# 100tqfpBreakout.net
KiCad netlist of a schematic drawn in EAGLE
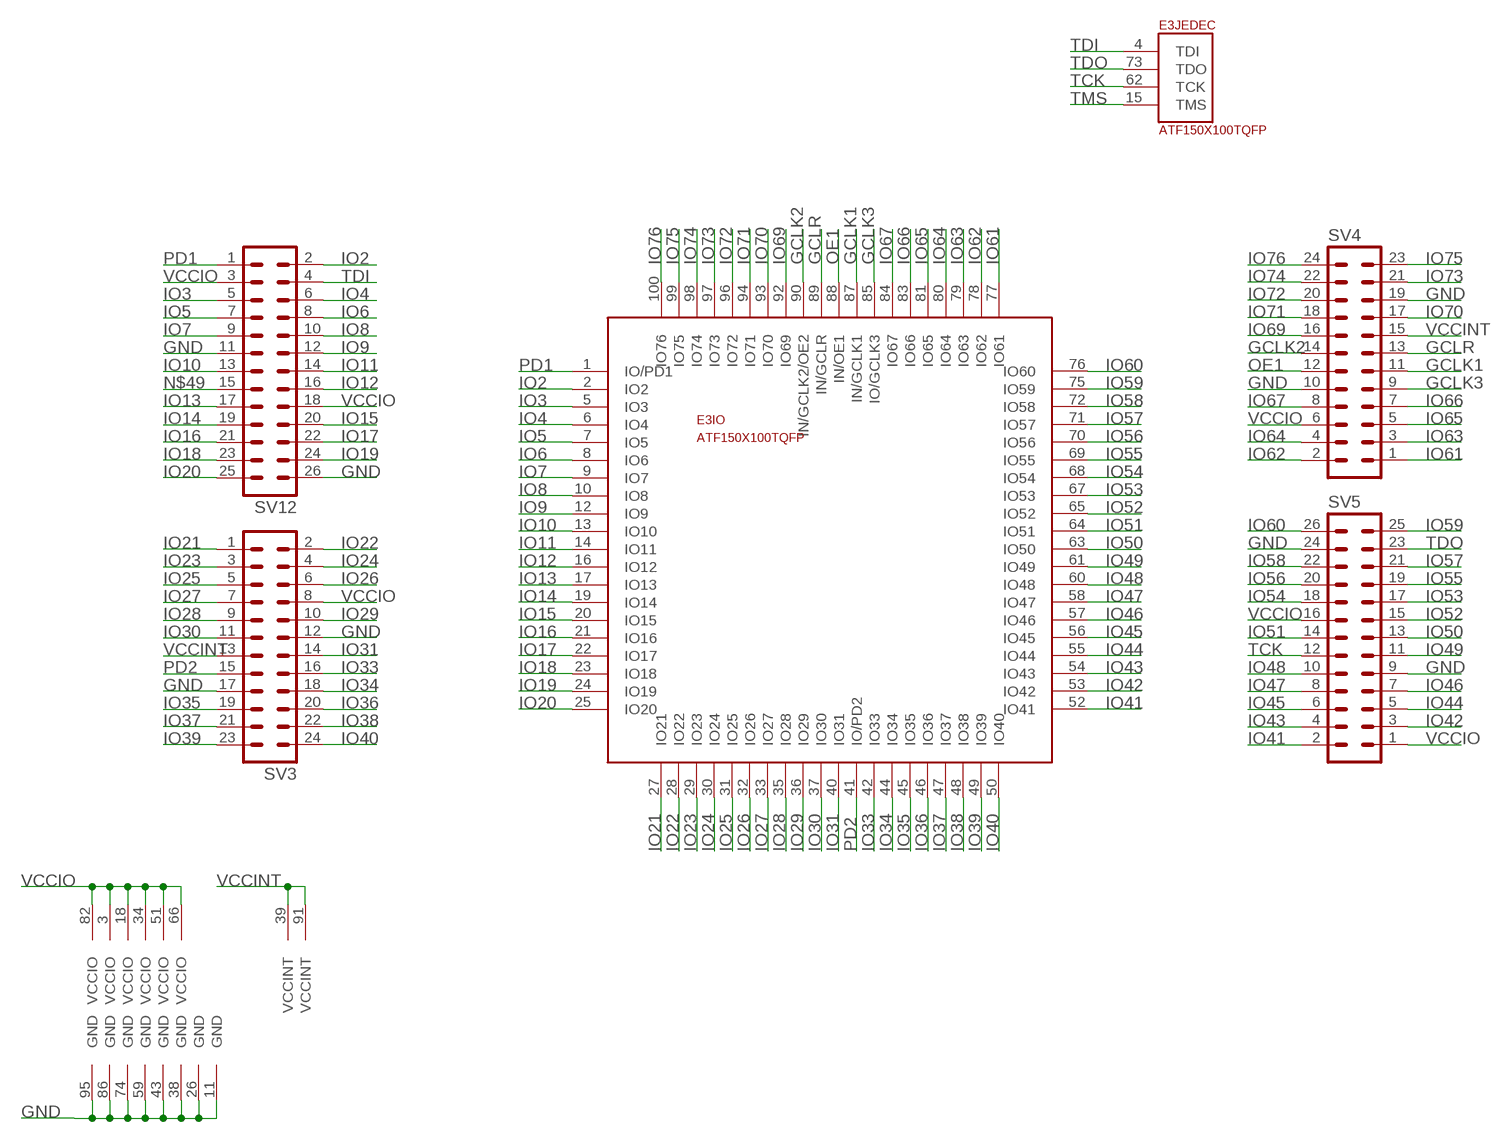
[diagram p0: schematic, sheet 1]

(export (version "E")
  (design (tool "Eeschema 10.0.6"))
  (components
    (comp (ref "E3")
      (value "ATF150X100TQFP")
      (footprint "eagle-import:TQFP-100")
      (libsource (lib "eagle-import") (part "ATF150X100TQFP"))
    )
    (comp (ref "SV3")
      (value "MA12-2")
      (footprint "eagle-import:MA12-2")
      (libsource (lib "eagle-import") (part "MA12-2"))
    )
    (comp (ref "SV4")
      (value "MA12-2")
      (footprint "eagle-import:MA12-2")
      (libsource (lib "eagle-import") (part "MA12-2"))
    )
    (comp (ref "SV5")
      (value "MA13-2")
      (footprint "eagle-import:MA13-2")
      (libsource (lib "eagle-import") (part "MA13-2"))
    )
    (comp (ref "SV12")
      (value "MA13-2")
      (footprint "eagle-import:MA13-2")
      (libsource (lib "eagle-import") (part "MA13-2"))
    )
  )
  (nets
    (net (code "1") (name "/GCLK1") (class "Default")
      (node (ref "E3") (pin "87") (pinfunction "IN/GCLK1_87") (pintype "input"))
      (node (ref "SV4") (pin "11") (pinfunction "11_11") (pintype "passive"))
    )
    (net (code "2") (name "/GCLK2") (class "Default")
      (node (ref "E3") (pin "90") (pinfunction "IN/GCLK2/OE2_90") (pintype "input"))
      (node (ref "SV4") (pin "14") (pinfunction "14_14") (pintype "passive"))
    )
    (net (code "3") (name "/GCLK3") (class "Default")
      (node (ref "E3") (pin "85") (pinfunction "IO/GCLK3_85") (pintype "bidirectional"))
      (node (ref "SV4") (pin "9") (pinfunction "9_9") (pintype "passive"))
    )
    (net (code "4") (name "/GCLR") (class "Default")
      (node (ref "E3") (pin "89") (pinfunction "IN/GCLR_89") (pintype "input"))
      (node (ref "SV4") (pin "13") (pinfunction "13_13") (pintype "passive"))
    )
    (net (code "5") (name "/GND") (class "Default")
      (node (ref "E3") (pin "11") (pinfunction "GND_11") (pintype "power_in"))
      (node (ref "E3") (pin "26") (pinfunction "GND_26") (pintype "power_in"))
      (node (ref "E3") (pin "38") (pinfunction "GND_38") (pintype "power_in"))
      (node (ref "E3") (pin "43") (pinfunction "GND_43") (pintype "power_in"))
      (node (ref "E3") (pin "59") (pinfunction "GND_59") (pintype "power_in"))
      (node (ref "E3") (pin "74") (pinfunction "GND_74") (pintype "power_in"))
      (node (ref "E3") (pin "86") (pinfunction "GND_86") (pintype "power_in"))
      (node (ref "E3") (pin "95") (pinfunction "GND_95") (pintype "power_in"))
      (node (ref "SV12") (pin "11") (pinfunction "11_11") (pintype "passive"))
      (node (ref "SV12") (pin "26") (pinfunction "26_26") (pintype "passive"))
      (node (ref "SV3") (pin "12") (pinfunction "12_12") (pintype "passive"))
      (node (ref "SV3") (pin "17") (pinfunction "17_17") (pintype "passive"))
      (node (ref "SV4") (pin "10") (pinfunction "10_10") (pintype "passive"))
      (node (ref "SV4") (pin "19") (pinfunction "19_19") (pintype "passive"))
      (node (ref "SV5") (pin "24") (pinfunction "24_24") (pintype "passive"))
      (node (ref "SV5") (pin "9") (pinfunction "9_9") (pintype "passive"))
    )
    (net (code "6") (name "/IO2") (class "Default")
      (node (ref "E3") (pin "2") (pinfunction "IO2_2") (pintype "bidirectional"))
      (node (ref "SV12") (pin "2") (pinfunction "2_2") (pintype "passive"))
    )
    (net (code "7") (name "/IO3") (class "Default")
      (node (ref "E3") (pin "5") (pinfunction "IO3_5") (pintype "bidirectional"))
      (node (ref "SV12") (pin "5") (pinfunction "5_5") (pintype "passive"))
    )
    (net (code "8") (name "/IO4") (class "Default")
      (node (ref "E3") (pin "6") (pinfunction "IO4_6") (pintype "bidirectional"))
      (node (ref "SV12") (pin "6") (pinfunction "6_6") (pintype "passive"))
    )
    (net (code "9") (name "/IO5") (class "Default")
      (node (ref "E3") (pin "7") (pinfunction "IO5_7") (pintype "bidirectional"))
      (node (ref "SV12") (pin "7") (pinfunction "7_7") (pintype "passive"))
    )
    (net (code "10") (name "/IO6") (class "Default")
      (node (ref "E3") (pin "8") (pinfunction "IO6_8") (pintype "bidirectional"))
      (node (ref "SV12") (pin "8") (pinfunction "8_8") (pintype "passive"))
    )
    (net (code "11") (name "/IO7") (class "Default")
      (node (ref "E3") (pin "9") (pinfunction "IO7_9") (pintype "bidirectional"))
      (node (ref "SV12") (pin "9") (pinfunction "9_9") (pintype "passive"))
    )
    (net (code "12") (name "/IO8") (class "Default")
      (node (ref "E3") (pin "10") (pinfunction "IO8_10") (pintype "bidirectional"))
      (node (ref "SV12") (pin "10") (pinfunction "10_10") (pintype "passive"))
    )
    (net (code "13") (name "/IO9") (class "Default")
      (node (ref "E3") (pin "12") (pinfunction "IO9_12") (pintype "bidirectional"))
      (node (ref "SV12") (pin "12") (pinfunction "12_12") (pintype "passive"))
    )
    (net (code "14") (name "/IO10") (class "Default")
      (node (ref "E3") (pin "13") (pinfunction "IO10_13") (pintype "bidirectional"))
      (node (ref "SV12") (pin "13") (pinfunction "13_13") (pintype "passive"))
    )
    (net (code "15") (name "/IO11") (class "Default")
      (node (ref "E3") (pin "14") (pinfunction "IO11_14") (pintype "bidirectional"))
      (node (ref "SV12") (pin "14") (pinfunction "14_14") (pintype "passive"))
    )
    (net (code "16") (name "/IO12") (class "Default")
      (node (ref "E3") (pin "16") (pinfunction "IO12_16") (pintype "bidirectional"))
      (node (ref "SV12") (pin "16") (pinfunction "16_16") (pintype "passive"))
    )
    (net (code "17") (name "/IO13") (class "Default")
      (node (ref "E3") (pin "17") (pinfunction "IO13_17") (pintype "bidirectional"))
      (node (ref "SV12") (pin "17") (pinfunction "17_17") (pintype "passive"))
    )
    (net (code "18") (name "/IO14") (class "Default")
      (node (ref "E3") (pin "19") (pinfunction "IO14_19") (pintype "bidirectional"))
      (node (ref "SV12") (pin "19") (pinfunction "19_19") (pintype "passive"))
    )
    (net (code "19") (name "/IO15") (class "Default")
      (node (ref "E3") (pin "20") (pinfunction "IO15_20") (pintype "bidirectional"))
      (node (ref "SV12") (pin "20") (pinfunction "20_20") (pintype "passive"))
    )
    (net (code "20") (name "/IO16") (class "Default")
      (node (ref "E3") (pin "21") (pinfunction "IO16_21") (pintype "bidirectional"))
      (node (ref "SV12") (pin "21") (pinfunction "21_21") (pintype "passive"))
    )
    (net (code "21") (name "/IO17") (class "Default")
      (node (ref "E3") (pin "22") (pinfunction "IO17_22") (pintype "bidirectional"))
      (node (ref "SV12") (pin "22") (pinfunction "22_22") (pintype "passive"))
    )
    (net (code "22") (name "/IO18") (class "Default")
      (node (ref "E3") (pin "23") (pinfunction "IO18_23") (pintype "bidirectional"))
      (node (ref "SV12") (pin "23") (pinfunction "23_23") (pintype "passive"))
    )
    (net (code "23") (name "/IO19") (class "Default")
      (node (ref "E3") (pin "24") (pinfunction "IO19_24") (pintype "bidirectional"))
      (node (ref "SV12") (pin "24") (pinfunction "24_24") (pintype "passive"))
    )
    (net (code "24") (name "/IO20") (class "Default")
      (node (ref "E3") (pin "25") (pinfunction "IO20_25") (pintype "bidirectional"))
      (node (ref "SV12") (pin "25") (pinfunction "25_25") (pintype "passive"))
    )
    (net (code "25") (name "/IO21") (class "Default")
      (node (ref "E3") (pin "27") (pinfunction "IO21_27") (pintype "bidirectional"))
      (node (ref "SV3") (pin "1") (pinfunction "1_1") (pintype "passive"))
    )
    (net (code "26") (name "/IO22") (class "Default")
      (node (ref "E3") (pin "28") (pinfunction "IO22_28") (pintype "bidirectional"))
      (node (ref "SV3") (pin "2") (pinfunction "2_2") (pintype "passive"))
    )
    (net (code "27") (name "/IO23") (class "Default")
      (node (ref "E3") (pin "29") (pinfunction "IO23_29") (pintype "bidirectional"))
      (node (ref "SV3") (pin "3") (pinfunction "3_3") (pintype "passive"))
    )
    (net (code "28") (name "/IO24") (class "Default")
      (node (ref "E3") (pin "30") (pinfunction "IO24_30") (pintype "bidirectional"))
      (node (ref "SV3") (pin "4") (pinfunction "4_4") (pintype "passive"))
    )
    (net (code "29") (name "/IO25") (class "Default")
      (node (ref "E3") (pin "31") (pinfunction "IO25_31") (pintype "bidirectional"))
      (node (ref "SV3") (pin "5") (pinfunction "5_5") (pintype "passive"))
    )
    (net (code "30") (name "/IO26") (class "Default")
      (node (ref "E3") (pin "32") (pinfunction "IO26_32") (pintype "bidirectional"))
      (node (ref "SV3") (pin "6") (pinfunction "6_6") (pintype "passive"))
    )
    (net (code "31") (name "/IO27") (class "Default")
      (node (ref "E3") (pin "33") (pinfunction "IO27_33") (pintype "bidirectional"))
      (node (ref "SV3") (pin "7") (pinfunction "7_7") (pintype "passive"))
    )
    (net (code "32") (name "/IO28") (class "Default")
      (node (ref "E3") (pin "35") (pinfunction "IO28_35") (pintype "bidirectional"))
      (node (ref "SV3") (pin "9") (pinfunction "9_9") (pintype "passive"))
    )
    (net (code "33") (name "/IO29") (class "Default")
      (node (ref "E3") (pin "36") (pinfunction "IO29_36") (pintype "bidirectional"))
      (node (ref "SV3") (pin "10") (pinfunction "10_10") (pintype "passive"))
    )
    (net (code "34") (name "/IO30") (class "Default")
      (node (ref "E3") (pin "37") (pinfunction "IO30_37") (pintype "bidirectional"))
      (node (ref "SV3") (pin "11") (pinfunction "11_11") (pintype "passive"))
    )
    (net (code "35") (name "/IO31") (class "Default")
      (node (ref "E3") (pin "40") (pinfunction "IO31_40") (pintype "bidirectional"))
      (node (ref "SV3") (pin "14") (pinfunction "14_14") (pintype "passive"))
    )
    (net (code "36") (name "/IO33") (class "Default")
      (node (ref "E3") (pin "42") (pinfunction "IO33_42") (pintype "bidirectional"))
      (node (ref "SV3") (pin "16") (pinfunction "16_16") (pintype "passive"))
    )
    (net (code "37") (name "/IO34") (class "Default")
      (node (ref "E3") (pin "44") (pinfunction "IO34_44") (pintype "bidirectional"))
      (node (ref "SV3") (pin "18") (pinfunction "18_18") (pintype "passive"))
    )
    (net (code "38") (name "/IO35") (class "Default")
      (node (ref "E3") (pin "45") (pinfunction "IO35_45") (pintype "bidirectional"))
      (node (ref "SV3") (pin "19") (pinfunction "19_19") (pintype "passive"))
    )
    (net (code "39") (name "/IO36") (class "Default")
      (node (ref "E3") (pin "46") (pinfunction "IO36_46") (pintype "bidirectional"))
      (node (ref "SV3") (pin "20") (pinfunction "20_20") (pintype "passive"))
    )
    (net (code "40") (name "/IO37") (class "Default")
      (node (ref "E3") (pin "47") (pinfunction "IO37_47") (pintype "bidirectional"))
      (node (ref "SV3") (pin "21") (pinfunction "21_21") (pintype "passive"))
    )
    (net (code "41") (name "/IO38") (class "Default")
      (node (ref "E3") (pin "48") (pinfunction "IO38_48") (pintype "bidirectional"))
      (node (ref "SV3") (pin "22") (pinfunction "22_22") (pintype "passive"))
    )
    (net (code "42") (name "/IO39") (class "Default")
      (node (ref "E3") (pin "49") (pinfunction "IO39_49") (pintype "bidirectional"))
      (node (ref "SV3") (pin "23") (pinfunction "23_23") (pintype "passive"))
    )
    (net (code "43") (name "/IO40") (class "Default")
      (node (ref "E3") (pin "50") (pinfunction "IO40_50") (pintype "bidirectional"))
      (node (ref "SV3") (pin "24") (pinfunction "24_24") (pintype "passive"))
    )
    (net (code "44") (name "/IO41") (class "Default")
      (node (ref "E3") (pin "52") (pinfunction "IO41_52") (pintype "bidirectional"))
      (node (ref "SV5") (pin "2") (pinfunction "2_2") (pintype "passive"))
    )
    (net (code "45") (name "/IO42") (class "Default")
      (node (ref "E3") (pin "53") (pinfunction "IO42_53") (pintype "bidirectional"))
      (node (ref "SV5") (pin "3") (pinfunction "3_3") (pintype "passive"))
    )
    (net (code "46") (name "/IO43") (class "Default")
      (node (ref "E3") (pin "54") (pinfunction "IO43_54") (pintype "bidirectional"))
      (node (ref "SV5") (pin "4") (pinfunction "4_4") (pintype "passive"))
    )
    (net (code "47") (name "/IO44") (class "Default")
      (node (ref "E3") (pin "55") (pinfunction "IO44_55") (pintype "bidirectional"))
      (node (ref "SV5") (pin "5") (pinfunction "5_5") (pintype "passive"))
    )
    (net (code "48") (name "/IO45") (class "Default")
      (node (ref "E3") (pin "56") (pinfunction "IO45_56") (pintype "bidirectional"))
      (node (ref "SV5") (pin "6") (pinfunction "6_6") (pintype "passive"))
    )
    (net (code "49") (name "/IO46") (class "Default")
      (node (ref "E3") (pin "57") (pinfunction "IO46_57") (pintype "bidirectional"))
      (node (ref "SV5") (pin "7") (pinfunction "7_7") (pintype "passive"))
    )
    (net (code "50") (name "/IO47") (class "Default")
      (node (ref "E3") (pin "58") (pinfunction "IO47_58") (pintype "bidirectional"))
      (node (ref "SV5") (pin "8") (pinfunction "8_8") (pintype "passive"))
    )
    (net (code "51") (name "/IO48") (class "Default")
      (node (ref "E3") (pin "60") (pinfunction "IO48_60") (pintype "bidirectional"))
      (node (ref "SV5") (pin "10") (pinfunction "10_10") (pintype "passive"))
    )
    (net (code "52") (name "/IO49") (class "Default")
      (node (ref "E3") (pin "61") (pinfunction "IO49_61") (pintype "bidirectional"))
      (node (ref "SV5") (pin "11") (pinfunction "11_11") (pintype "passive"))
    )
    (net (code "53") (name "/IO50") (class "Default")
      (node (ref "E3") (pin "63") (pinfunction "IO50_63") (pintype "bidirectional"))
      (node (ref "SV5") (pin "13") (pinfunction "13_13") (pintype "passive"))
    )
    (net (code "54") (name "/IO51") (class "Default")
      (node (ref "E3") (pin "64") (pinfunction "IO51_64") (pintype "bidirectional"))
      (node (ref "SV5") (pin "14") (pinfunction "14_14") (pintype "passive"))
    )
    (net (code "55") (name "/IO52") (class "Default")
      (node (ref "E3") (pin "65") (pinfunction "IO52_65") (pintype "bidirectional"))
      (node (ref "SV5") (pin "15") (pinfunction "15_15") (pintype "passive"))
    )
    (net (code "56") (name "/IO53") (class "Default")
      (node (ref "E3") (pin "67") (pinfunction "IO53_67") (pintype "bidirectional"))
      (node (ref "SV5") (pin "17") (pinfunction "17_17") (pintype "passive"))
    )
    (net (code "57") (name "/IO54") (class "Default")
      (node (ref "E3") (pin "68") (pinfunction "IO54_68") (pintype "bidirectional"))
      (node (ref "SV5") (pin "18") (pinfunction "18_18") (pintype "passive"))
    )
    (net (code "58") (name "/IO55") (class "Default")
      (node (ref "E3") (pin "69") (pinfunction "IO55_69") (pintype "bidirectional"))
      (node (ref "SV5") (pin "19") (pinfunction "19_19") (pintype "passive"))
    )
    (net (code "59") (name "/IO56") (class "Default")
      (node (ref "E3") (pin "70") (pinfunction "IO56_70") (pintype "bidirectional"))
      (node (ref "SV5") (pin "20") (pinfunction "20_20") (pintype "passive"))
    )
    (net (code "60") (name "/IO57") (class "Default")
      (node (ref "E3") (pin "71") (pinfunction "IO57_71") (pintype "bidirectional"))
      (node (ref "SV5") (pin "21") (pinfunction "21_21") (pintype "passive"))
    )
    (net (code "61") (name "/IO58") (class "Default")
      (node (ref "E3") (pin "72") (pinfunction "IO58_72") (pintype "bidirectional"))
      (node (ref "SV5") (pin "22") (pinfunction "22_22") (pintype "passive"))
    )
    (net (code "62") (name "/IO59") (class "Default")
      (node (ref "E3") (pin "75") (pinfunction "IO59_75") (pintype "bidirectional"))
      (node (ref "SV5") (pin "25") (pinfunction "25_25") (pintype "passive"))
    )
    (net (code "63") (name "/IO60") (class "Default")
      (node (ref "E3") (pin "76") (pinfunction "IO60_76") (pintype "bidirectional"))
      (node (ref "SV5") (pin "26") (pinfunction "26_26") (pintype "passive"))
    )
    (net (code "64") (name "/IO61") (class "Default")
      (node (ref "E3") (pin "77") (pinfunction "IO61_77") (pintype "bidirectional"))
      (node (ref "SV4") (pin "1") (pinfunction "1_1") (pintype "passive"))
    )
    (net (code "65") (name "/IO62") (class "Default")
      (node (ref "E3") (pin "78") (pinfunction "IO62_78") (pintype "bidirectional"))
      (node (ref "SV4") (pin "2") (pinfunction "2_2") (pintype "passive"))
    )
    (net (code "66") (name "/IO63") (class "Default")
      (node (ref "E3") (pin "79") (pinfunction "IO63_79") (pintype "bidirectional"))
      (node (ref "SV4") (pin "3") (pinfunction "3_3") (pintype "passive"))
    )
    (net (code "67") (name "/IO64") (class "Default")
      (node (ref "E3") (pin "80") (pinfunction "IO64_80") (pintype "bidirectional"))
      (node (ref "SV4") (pin "4") (pinfunction "4_4") (pintype "passive"))
    )
    (net (code "68") (name "/IO65") (class "Default")
      (node (ref "E3") (pin "81") (pinfunction "IO65_81") (pintype "bidirectional"))
      (node (ref "SV4") (pin "5") (pinfunction "5_5") (pintype "passive"))
    )
    (net (code "69") (name "/IO66") (class "Default")
      (node (ref "E3") (pin "83") (pinfunction "IO66_83") (pintype "bidirectional"))
      (node (ref "SV4") (pin "7") (pinfunction "7_7") (pintype "passive"))
    )
    (net (code "70") (name "/IO67") (class "Default")
      (node (ref "E3") (pin "84") (pinfunction "IO67_84") (pintype "bidirectional"))
      (node (ref "SV4") (pin "8") (pinfunction "8_8") (pintype "passive"))
    )
    (net (code "71") (name "/IO69") (class "Default")
      (node (ref "E3") (pin "92") (pinfunction "IO69_92") (pintype "bidirectional"))
      (node (ref "SV4") (pin "16") (pinfunction "16_16") (pintype "passive"))
    )
    (net (code "72") (name "/IO70") (class "Default")
      (node (ref "E3") (pin "93") (pinfunction "IO70_93") (pintype "bidirectional"))
      (node (ref "SV4") (pin "17") (pinfunction "17_17") (pintype "passive"))
    )
    (net (code "73") (name "/IO71") (class "Default")
      (node (ref "E3") (pin "94") (pinfunction "IO71_94") (pintype "bidirectional"))
      (node (ref "SV4") (pin "18") (pinfunction "18_18") (pintype "passive"))
    )
    (net (code "74") (name "/IO72") (class "Default")
      (node (ref "E3") (pin "96") (pinfunction "IO72_96") (pintype "bidirectional"))
      (node (ref "SV4") (pin "20") (pinfunction "20_20") (pintype "passive"))
    )
    (net (code "75") (name "/IO73") (class "Default")
      (node (ref "E3") (pin "97") (pinfunction "IO73_97") (pintype "bidirectional"))
      (node (ref "SV4") (pin "21") (pinfunction "21_21") (pintype "passive"))
    )
    (net (code "76") (name "/IO74") (class "Default")
      (node (ref "E3") (pin "98") (pinfunction "IO74_98") (pintype "bidirectional"))
      (node (ref "SV4") (pin "22") (pinfunction "22_22") (pintype "passive"))
    )
    (net (code "77") (name "/IO75") (class "Default")
      (node (ref "E3") (pin "99") (pinfunction "IO75_99") (pintype "bidirectional"))
      (node (ref "SV4") (pin "23") (pinfunction "23_23") (pintype "passive"))
    )
    (net (code "78") (name "/IO76") (class "Default")
      (node (ref "E3") (pin "100") (pinfunction "IO76_100") (pintype "bidirectional"))
      (node (ref "SV4") (pin "24") (pinfunction "24_24") (pintype "passive"))
    )
    (net (code "79") (name "/N$49") (class "Default")
      (node (ref "SV12") (pin "15") (pinfunction "15_15") (pintype "passive"))
    )
    (net (code "80") (name "/OE1") (class "Default")
      (node (ref "E3") (pin "88") (pinfunction "IN/OE1_88") (pintype "input"))
      (node (ref "SV4") (pin "12") (pinfunction "12_12") (pintype "passive"))
    )
    (net (code "81") (name "/PD1") (class "Default")
      (node (ref "E3") (pin "1") (pinfunction "IO/PD1_1") (pintype "bidirectional"))
      (node (ref "SV12") (pin "1") (pinfunction "1_1") (pintype "passive"))
    )
    (net (code "82") (name "/PD2") (class "Default")
      (node (ref "E3") (pin "41") (pinfunction "IO/PD2_41") (pintype "bidirectional"))
      (node (ref "SV3") (pin "15") (pinfunction "15_15") (pintype "passive"))
    )
    (net (code "83") (name "/TCK") (class "Default")
      (node (ref "E3") (pin "62") (pinfunction "TCK_62") (pintype "bidirectional"))
      (node (ref "SV5") (pin "12") (pinfunction "12_12") (pintype "passive"))
    )
    (net (code "84") (name "/TDI") (class "Default")
      (node (ref "E3") (pin "4") (pinfunction "TDI_4") (pintype "bidirectional"))
      (node (ref "SV12") (pin "4") (pinfunction "4_4") (pintype "passive"))
    )
    (net (code "85") (name "/TDO") (class "Default")
      (node (ref "E3") (pin "73") (pinfunction "TDO_73") (pintype "bidirectional"))
      (node (ref "SV5") (pin "23") (pinfunction "23_23") (pintype "passive"))
    )
    (net (code "86") (name "/TMS") (class "Default")
      (node (ref "E3") (pin "15") (pinfunction "TMS_15") (pintype "bidirectional"))
    )
    (net (code "87") (name "/VCCINT") (class "Default")
      (node (ref "E3") (pin "39") (pinfunction "VCCINT_39") (pintype "power_in"))
      (node (ref "E3") (pin "91") (pinfunction "VCCINT_91") (pintype "power_in"))
      (node (ref "SV3") (pin "13") (pinfunction "13_13") (pintype "passive"))
      (node (ref "SV4") (pin "15") (pinfunction "15_15") (pintype "passive"))
    )
    (net (code "88") (name "/VCCIO") (class "Default")
      (node (ref "E3") (pin "18") (pinfunction "VCCIO_18") (pintype "power_in"))
      (node (ref "E3") (pin "3") (pinfunction "VCCIO_3") (pintype "power_in"))
      (node (ref "E3") (pin "34") (pinfunction "VCCIO_34") (pintype "power_in"))
      (node (ref "E3") (pin "51") (pinfunction "VCCIO_51") (pintype "power_in"))
      (node (ref "E3") (pin "66") (pinfunction "VCCIO_66") (pintype "power_in"))
      (node (ref "E3") (pin "82") (pinfunction "VCCIO_82") (pintype "power_in"))
      (node (ref "SV12") (pin "18") (pinfunction "18_18") (pintype "passive"))
      (node (ref "SV12") (pin "3") (pinfunction "3_3") (pintype "passive"))
      (node (ref "SV3") (pin "8") (pinfunction "8_8") (pintype "passive"))
      (node (ref "SV4") (pin "6") (pinfunction "6_6") (pintype "passive"))
      (node (ref "SV5") (pin "1") (pinfunction "1_1") (pintype "passive"))
      (node (ref "SV5") (pin "16") (pinfunction "16_16") (pintype "passive"))
    )
  )
)
